# bb8.net
KiCad netlist of a schematic drawn in EAGLE
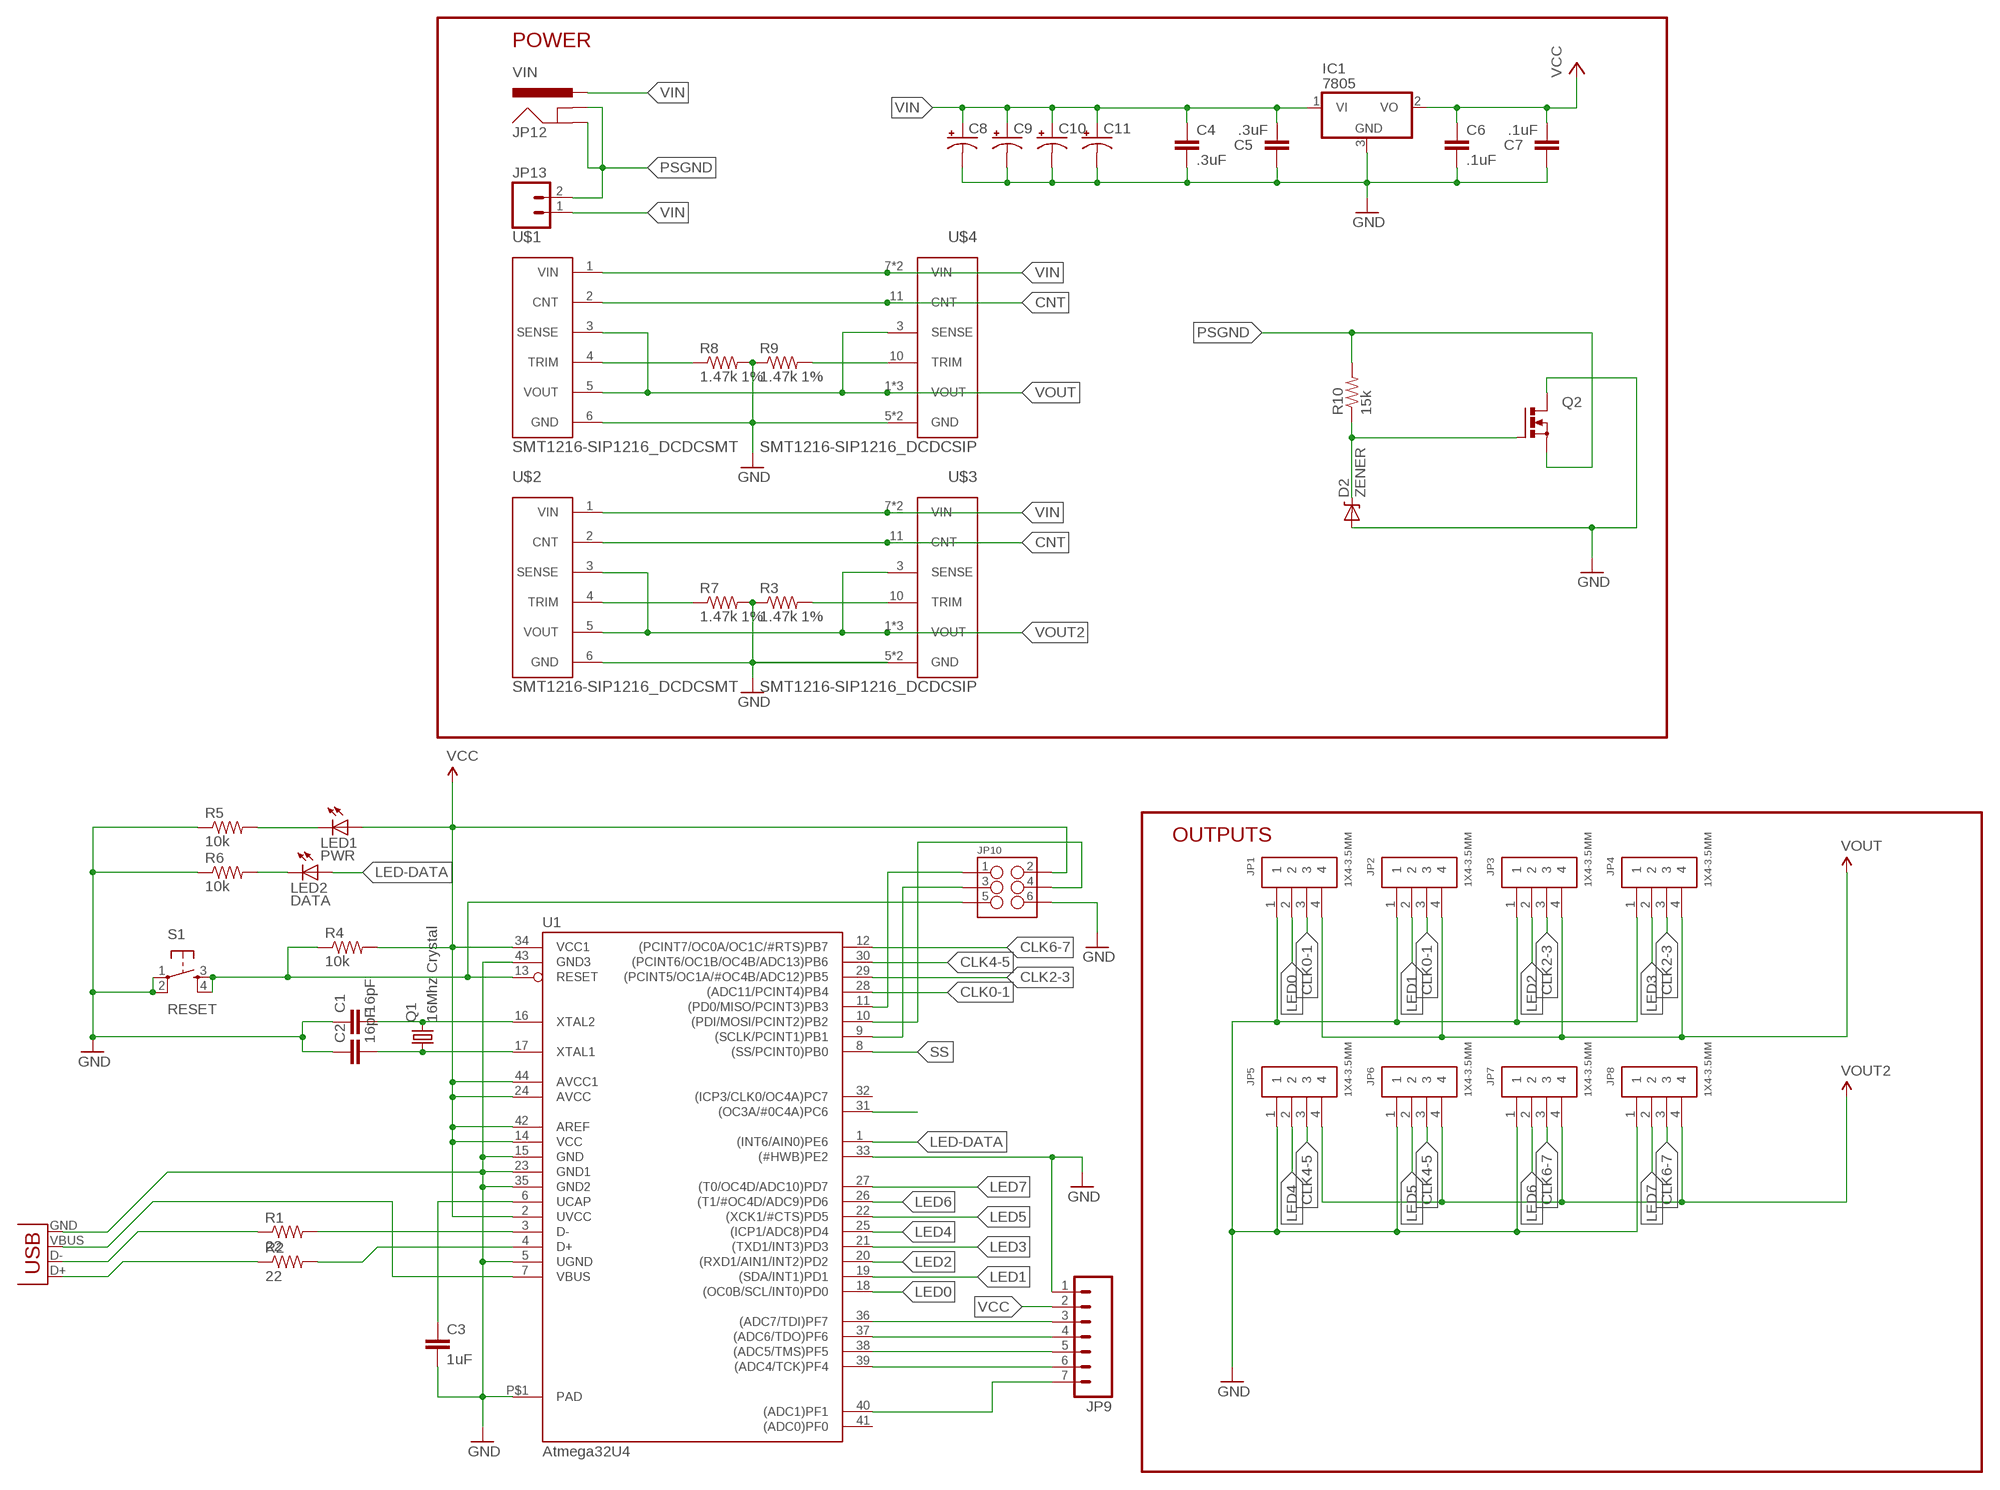
[diagram p0: schematic, sheet 1]

(export (version "E")
  (design (tool "Eeschema 10.0.6"))
  (components
    (comp (ref "C1")
      (value "16pF")
      (footprint "eagle-import:0805")
      (libsource (lib "eagle-import") (part "SparkFun-Passives_CAP0805"))
    )
    (comp (ref "C2")
      (value "16pF")
      (footprint "eagle-import:0805")
      (libsource (lib "eagle-import") (part "SparkFun-Passives_CAP0805"))
    )
    (comp (ref "C3")
      (value "1uF")
      (footprint "eagle-import:0805")
      (libsource (lib "eagle-import") (part "1UF-25V-10%(0805)"))
    )
    (comp (ref "C4")
      (value ".3uF")
      (footprint "eagle-import:1210")
      (libsource (lib "eagle-import") (part "CAP1210"))
    )
    (comp (ref "C5")
      (value ".3uF")
      (footprint "eagle-import:0805")
      (libsource (lib "eagle-import") (part "CAP0805"))
    )
    (comp (ref "C6")
      (value ".1uF")
      (footprint "eagle-import:1210")
      (libsource (lib "eagle-import") (part "CAP1210"))
    )
    (comp (ref "C7")
      (value ".1uF")
      (footprint "eagle-import:0805")
      (libsource (lib "eagle-import") (part "CAP0805"))
    )
    (comp (ref "C8")
      (value "CAP_POLE")
      (footprint "eagle-import:PANASONIC_E")
      (libsource (lib "eagle-import") (part "CAP_POLE"))
    )
    (comp (ref "C9")
      (value "CAP_POLE")
      (footprint "eagle-import:PANASONIC_E")
      (libsource (lib "eagle-import") (part "CAP_POLE"))
    )
    (comp (ref "C10")
      (value "CAP_POLE")
      (footprint "eagle-import:PANASONIC_E")
      (libsource (lib "eagle-import") (part "CAP_POLE"))
    )
    (comp (ref "C11")
      (value "CAP_POLE")
      (footprint "eagle-import:PANASONIC_E")
      (libsource (lib "eagle-import") (part "CAP_POLE"))
    )
    (comp (ref "D2")
      (value "ZENER")
      (footprint "eagle-import:SOD-323")
      (libsource (lib "eagle-import") (part "DIODE-ZENER-BZT52"))
    )
    (comp (ref "IC1")
      (value "7805")
      (footprint "eagle-import:TO252")
      (libsource (lib "eagle-import") (part "78DT06"))
    )
    (comp (ref "JP1")
      (value "1X4-3.5MM")
      (footprint "eagle-import:1X04-3.5MM")
      (libsource (lib "eagle-import") (part "1X4-3.5MM"))
    )
    (comp (ref "JP2")
      (value "1X4-3.5MM")
      (footprint "eagle-import:1X04-3.5MM")
      (libsource (lib "eagle-import") (part "1X4-3.5MM"))
    )
    (comp (ref "JP3")
      (value "1X4-3.5MM")
      (footprint "eagle-import:1X04-3.5MM")
      (libsource (lib "eagle-import") (part "1X4-3.5MM"))
    )
    (comp (ref "JP4")
      (value "1X4-3.5MM")
      (footprint "eagle-import:1X04-3.5MM")
      (libsource (lib "eagle-import") (part "1X4-3.5MM"))
    )
    (comp (ref "JP5")
      (value "1X4-3.5MM")
      (footprint "eagle-import:1X04-3.5MM")
      (libsource (lib "eagle-import") (part "1X4-3.5MM"))
    )
    (comp (ref "JP6")
      (value "1X4-3.5MM")
      (footprint "eagle-import:1X04-3.5MM")
      (libsource (lib "eagle-import") (part "1X4-3.5MM"))
    )
    (comp (ref "JP7")
      (value "1X4-3.5MM")
      (footprint "eagle-import:1X04-3.5MM")
      (libsource (lib "eagle-import") (part "1X4-3.5MM"))
    )
    (comp (ref "JP8")
      (value "1X4-3.5MM")
      (footprint "eagle-import:1X04-3.5MM")
      (libsource (lib "eagle-import") (part "1X4-3.5MM"))
    )
    (comp (ref "JP9")
      (value "M07")
      (footprint "eagle-import:1X07")
      (libsource (lib "eagle-import") (part "M07"))
    )
    (comp (ref "JP10")
      (value "M03X2POGO_PINS")
      (footprint "eagle-import:2X3_POGO")
      (libsource (lib "eagle-import") (part "M03X2POGO_PINS"))
    )
    (comp (ref "JP11")
      (value "USB-B")
      (footprint "eagle-import:USB-B-PTH")
      (libsource (lib "eagle-import") (part "USBPTH"))
    )
    (comp (ref "JP12")
      (value "VIN")
      (footprint "eagle-import:POWER_JACK_PTH_LOCK")
      (libsource (lib "eagle-import") (part "POWER_JACKPTH_LOCK"))
    )
    (comp (ref "JP13")
      (value "M025MM")
      (footprint "eagle-import:SCREWTERMINAL-5MM-2")
      (libsource (lib "eagle-import") (part "M025MM"))
    )
    (comp (ref "LED1")
      (value "PWR")
      (footprint "eagle-import:LED3MM")
      (libsource (lib "eagle-import") (part "LED3MM"))
    )
    (comp (ref "LED2")
      (value "DATA")
      (footprint "eagle-import:LED3MM")
      (libsource (lib "eagle-import") (part "LED3MM"))
    )
    (comp (ref "Q1")
      (value "16Mhz Crystal")
      (footprint "eagle-import:XS3225")
      (libsource (lib "eagle-import") (part "CRYSTAL"))
    )
    (comp (ref "Q2")
      (value "PMOSFET_NTO220BV")
      (footprint "eagle-import:TO220BV")
      (libsource (lib "eagle-import") (part "PMOSFET_NTO220BV"))
    )
    (comp (ref "R1")
      (value "22")
      (footprint "eagle-import:0805")
      (libsource (lib "eagle-import") (part "RESISTOR0805-RES"))
    )
    (comp (ref "R2")
      (value "22")
      (footprint "eagle-import:0805")
      (libsource (lib "eagle-import") (part "RESISTOR0805-RES"))
    )
    (comp (ref "R3")
      (value "1.47k 1%")
      (footprint "eagle-import:0805")
      (libsource (lib "eagle-import") (part "RESISTOR0805-RES"))
    )
    (comp (ref "R4")
      (value "10k")
      (footprint "eagle-import:0805")
      (libsource (lib "eagle-import") (part "RESISTOR0805-RES"))
    )
    (comp (ref "R5")
      (value "10k")
      (footprint "eagle-import:0805")
      (libsource (lib "eagle-import") (part "RESISTOR0805-RES"))
    )
    (comp (ref "R6")
      (value "10k")
      (footprint "eagle-import:0805")
      (libsource (lib "eagle-import") (part "RESISTOR0805-RES"))
    )
    (comp (ref "R7")
      (value "1.47k 1%")
      (footprint "eagle-import:0805")
      (libsource (lib "eagle-import") (part "RESISTOR0805-RES"))
    )
    (comp (ref "R8")
      (value "1.47k 1%")
      (footprint "eagle-import:0805")
      (libsource (lib "eagle-import") (part "RESISTOR0805-RES"))
    )
    (comp (ref "R9")
      (value "1.47k 1%")
      (footprint "eagle-import:0805")
      (libsource (lib "eagle-import") (part "RESISTOR0805-RES"))
    )
    (comp (ref "R10")
      (value "15k")
      (footprint "eagle-import:0805")
      (libsource (lib "eagle-import") (part "RESISTOR0805-RES"))
    )
    (comp (ref "S1")
      (value "RESET")
      (footprint "eagle-import:TACTILE_SWITCH_SMD")
      (libsource (lib "eagle-import") (part "TAC_SWITCHSMD"))
    )
    (comp (ref "U$1")
      (value "SMT1216-SIP1216_DCDCSMT")
      (footprint "eagle-import:SMT1216_DCDC")
      (libsource (lib "eagle-import") (part "SMT1216-SIP1216_DCDCSMT"))
    )
    (comp (ref "U$2")
      (value "SMT1216-SIP1216_DCDCSMT")
      (footprint "eagle-import:SMT1216_DCDC")
      (libsource (lib "eagle-import") (part "SMT1216-SIP1216_DCDCSMT"))
    )
    (comp (ref "U$3")
      (value "SMT1216-SIP1216_DCDCSIP")
      (footprint "eagle-import:SIP1216_DCDC")
      (libsource (lib "eagle-import") (part "SMT1216-SIP1216_DCDCSIP"))
    )
    (comp (ref "U$4")
      (value "SMT1216-SIP1216_DCDCSIP")
      (footprint "eagle-import:SIP1216_DCDC")
      (libsource (lib "eagle-import") (part "SMT1216-SIP1216_DCDCSIP"))
    )
    (comp (ref "U1")
      (value "Atmega32U4")
      (footprint "eagle-import:ARDUINO_LEONARDO-REV3B_SMARTPRJ_TQFP44-PAD")
      (libsource (lib "eagle-import") (part "ARDUINO_LEONARDO-REV3B_SMARTPRJ_ATMEGA32U4-XUAU"))
    )
  )
  (nets
    (net (code "1") (name "CLK0-1") (class "Default")
      (node (ref "JP1") (pin "3") (pinfunction "3_3") (pintype "bidirectional"))
      (node (ref "JP2") (pin "3") (pinfunction "3_3") (pintype "bidirectional"))
      (node (ref "U1") (pin "28") (pinfunction "(ADC11/PCINT4)PB4_28") (pintype "bidirectional"))
    )
    (net (code "2") (name "CLK2-3") (class "Default")
      (node (ref "JP3") (pin "3") (pinfunction "3_3") (pintype "bidirectional"))
      (node (ref "JP4") (pin "3") (pinfunction "3_3") (pintype "bidirectional"))
      (node (ref "U1") (pin "29") (pinfunction "(PCINT5/OC1A/#OC4B/ADC12)PB5_29") (pintype "bidirectional"))
    )
    (net (code "3") (name "CLK4-5") (class "Default")
      (node (ref "JP5") (pin "3") (pinfunction "3_3") (pintype "bidirectional"))
      (node (ref "JP6") (pin "3") (pinfunction "3_3") (pintype "bidirectional"))
      (node (ref "U1") (pin "30") (pinfunction "(PCINT6/OC1B/OC4B/ADC13)PB6_30") (pintype "bidirectional"))
    )
    (net (code "4") (name "CLK6-7") (class "Default")
      (node (ref "JP7") (pin "3") (pinfunction "3_3") (pintype "bidirectional"))
      (node (ref "JP8") (pin "3") (pinfunction "3_3") (pintype "bidirectional"))
      (node (ref "U1") (pin "12") (pinfunction "(PCINT7/OC0A/OC1C/#RTS)PB7_12") (pintype "bidirectional"))
    )
    (net (code "5") (name "CNT") (class "Default")
      (node (ref "U$1") (pin "2") (pinfunction "CNT_2") (pintype "bidirectional"))
      (node (ref "U$2") (pin "2") (pinfunction "CNT_2") (pintype "bidirectional"))
      (node (ref "U$3") (pin "11") (pinfunction "CNT_11") (pintype "bidirectional"))
      (node (ref "U$4") (pin "11") (pinfunction "CNT_11") (pintype "bidirectional"))
      (node (ref "U1") (pin "31") (pinfunction "(OC3A/#0C4A)PC6_31") (pintype "bidirectional"))
    )
    (net (code "6") (name "GND") (class "Default")
      (node (ref "C1") (pin "1") (pinfunction "1_1") (pintype "passive"))
      (node (ref "C10") (pin "-") (pinfunction "-_-") (pintype "passive"))
      (node (ref "C11") (pin "-") (pinfunction "-_-") (pintype "passive"))
      (node (ref "C2") (pin "1") (pinfunction "1_1") (pintype "passive"))
      (node (ref "C3") (pin "2") (pinfunction "2_2") (pintype "passive"))
      (node (ref "C4") (pin "2") (pinfunction "2_2") (pintype "passive"))
      (node (ref "C5") (pin "1") (pinfunction "1_1") (pintype "passive"))
      (node (ref "C6") (pin "2") (pinfunction "2_2") (pintype "passive"))
      (node (ref "C7") (pin "1") (pinfunction "1_1") (pintype "passive"))
      (node (ref "C8") (pin "-") (pinfunction "-_-") (pintype "passive"))
      (node (ref "C9") (pin "-") (pinfunction "-_-") (pintype "passive"))
      (node (ref "D2") (pin "2") (pinfunction "A_2") (pintype "passive"))
      (node (ref "IC1") (pin "3") (pinfunction "GND_3") (pintype "passive"))
      (node (ref "JP1") (pin "1") (pinfunction "1_1") (pintype "bidirectional"))
      (node (ref "JP10") (pin "P$6") (pinfunction "6_P$6") (pintype "bidirectional"))
      (node (ref "JP11") (pin "GND") (pinfunction "GND_GND") (pintype "bidirectional"))
      (node (ref "JP2") (pin "1") (pinfunction "1_1") (pintype "bidirectional"))
      (node (ref "JP3") (pin "1") (pinfunction "1_1") (pintype "bidirectional"))
      (node (ref "JP4") (pin "1") (pinfunction "1_1") (pintype "bidirectional"))
      (node (ref "JP5") (pin "1") (pinfunction "1_1") (pintype "bidirectional"))
      (node (ref "JP6") (pin "1") (pinfunction "1_1") (pintype "bidirectional"))
      (node (ref "JP7") (pin "1") (pinfunction "1_1") (pintype "bidirectional"))
      (node (ref "JP8") (pin "1") (pinfunction "1_1") (pintype "bidirectional"))
      (node (ref "JP9") (pin "1") (pinfunction "1_1") (pintype "passive"))
      (node (ref "Q2") (pin "D") (pinfunction "D_D") (pintype "passive"))
      (node (ref "R3") (pin "1") (pinfunction "1_1") (pintype "passive"))
      (node (ref "R5") (pin "1") (pinfunction "1_1") (pintype "passive"))
      (node (ref "R6") (pin "1") (pinfunction "1_1") (pintype "passive"))
      (node (ref "R7") (pin "2") (pinfunction "2_2") (pintype "passive"))
      (node (ref "R8") (pin "2") (pinfunction "2_2") (pintype "passive"))
      (node (ref "R9") (pin "1") (pinfunction "1_1") (pintype "passive"))
      (node (ref "S1") (pin "1") (pinfunction "1_1") (pintype "passive"))
      (node (ref "S1") (pin "2") (pinfunction "2_2") (pintype "passive"))
      (node (ref "U$1") (pin "6") (pinfunction "GND_6") (pintype "bidirectional"))
      (node (ref "U$2") (pin "6") (pinfunction "GND_6") (pintype "bidirectional"))
      (node (ref "U$3") (pin "5") (pinfunction "GND_5") (pintype "bidirectional"))
      (node (ref "U$3") (pin "6") (pinfunction "GND_6") (pintype "bidirectional"))
      (node (ref "U$4") (pin "5") (pinfunction "GND_5") (pintype "bidirectional"))
      (node (ref "U$4") (pin "6") (pinfunction "GND_6") (pintype "bidirectional"))
      (node (ref "U1") (pin "15") (pinfunction "GND_15") (pintype "power_in"))
      (node (ref "U1") (pin "23") (pinfunction "GND1_23") (pintype "power_in"))
      (node (ref "U1") (pin "33") (pinfunction "(#HWB)PE2_33") (pintype "bidirectional"))
      (node (ref "U1") (pin "35") (pinfunction "GND2_35") (pintype "power_in"))
      (node (ref "U1") (pin "43") (pinfunction "GND3_43") (pintype "power_in"))
      (node (ref "U1") (pin "5") (pinfunction "UGND_5") (pintype "power_in"))
      (node (ref "U1") (pin "P$1") (pinfunction "PAD_P$1") (pintype "power_in"))
    )
    (net (code "7") (name "LED-DATA") (class "Default")
      (node (ref "LED2") (pin "A") (pinfunction "A_A") (pintype "passive"))
      (node (ref "U1") (pin "1") (pinfunction "(INT6/AIN0)PE6_1") (pintype "bidirectional"))
    )
    (net (code "8") (name "LED0") (class "Default")
      (node (ref "JP1") (pin "2") (pinfunction "2_2") (pintype "bidirectional"))
      (node (ref "U1") (pin "18") (pinfunction "(OC0B/SCL/INT0)PD0_18") (pintype "bidirectional"))
    )
    (net (code "9") (name "LED1") (class "Default")
      (node (ref "JP2") (pin "2") (pinfunction "2_2") (pintype "bidirectional"))
      (node (ref "U1") (pin "19") (pinfunction "(SDA/INT1)PD1_19") (pintype "bidirectional"))
    )
    (net (code "10") (name "LED2") (class "Default")
      (node (ref "JP3") (pin "2") (pinfunction "2_2") (pintype "bidirectional"))
      (node (ref "U1") (pin "20") (pinfunction "(RXD1/AIN1/INT2)PD2_20") (pintype "bidirectional"))
    )
    (net (code "11") (name "LED3") (class "Default")
      (node (ref "JP4") (pin "2") (pinfunction "2_2") (pintype "bidirectional"))
      (node (ref "U1") (pin "21") (pinfunction "(TXD1/INT3)PD3_21") (pintype "bidirectional"))
    )
    (net (code "12") (name "LED4") (class "Default")
      (node (ref "JP5") (pin "2") (pinfunction "2_2") (pintype "bidirectional"))
      (node (ref "U1") (pin "25") (pinfunction "(ICP1/ADC8)PD4_25") (pintype "bidirectional"))
    )
    (net (code "13") (name "LED5") (class "Default")
      (node (ref "JP6") (pin "2") (pinfunction "2_2") (pintype "bidirectional"))
      (node (ref "U1") (pin "22") (pinfunction "(XCK1/#CTS)PD5_22") (pintype "bidirectional"))
    )
    (net (code "14") (name "LED6") (class "Default")
      (node (ref "JP7") (pin "2") (pinfunction "2_2") (pintype "bidirectional"))
      (node (ref "U1") (pin "26") (pinfunction "(T1/#OC4D/ADC9)PD6_26") (pintype "bidirectional"))
    )
    (net (code "15") (name "LED7") (class "Default")
      (node (ref "JP8") (pin "2") (pinfunction "2_2") (pintype "bidirectional"))
      (node (ref "U1") (pin "27") (pinfunction "(T0/OC4D/ADC10)PD7_27") (pintype "bidirectional"))
    )
    (net (code "16") (name "Net-(D2-C)") (class "Default")
      (node (ref "D2") (pin "1") (pinfunction "C_1") (pintype "passive"))
      (node (ref "Q2") (pin "G") (pinfunction "G_G") (pintype "passive"))
      (node (ref "R10") (pin "1") (pinfunction "1_1") (pintype "passive"))
    )
    (net (code "17") (name "Net-(JP10-1)") (class "Default")
      (node (ref "JP10") (pin "P$1") (pinfunction "1_P$1") (pintype "bidirectional"))
      (node (ref "U1") (pin "11") (pinfunction "(PD0/MISO/PCINT3)PB3_11") (pintype "bidirectional"))
    )
    (net (code "18") (name "Net-(JP10-3)") (class "Default")
      (node (ref "JP10") (pin "P$3") (pinfunction "3_P$3") (pintype "bidirectional"))
      (node (ref "U1") (pin "9") (pinfunction "(SCLK/PCINT1)PB1_9") (pintype "bidirectional"))
    )
    (net (code "19") (name "Net-(JP10-4)") (class "Default")
      (node (ref "JP10") (pin "P$4") (pinfunction "4_P$4") (pintype "bidirectional"))
      (node (ref "U1") (pin "10") (pinfunction "(PDI/MOSI/PCINT2)PB2_10") (pintype "bidirectional"))
    )
    (net (code "20") (name "Net-(JP10-5)") (class "Default")
      (node (ref "JP10") (pin "P$5") (pinfunction "5_P$5") (pintype "bidirectional"))
      (node (ref "R4") (pin "1") (pinfunction "1_1") (pintype "passive"))
      (node (ref "S1") (pin "3") (pinfunction "3_3") (pintype "passive"))
      (node (ref "S1") (pin "4") (pinfunction "4_4") (pintype "passive"))
      (node (ref "U1") (pin "13") (pinfunction "RESET_13") (pintype "input"))
    )
    (net (code "21") (name "Net-(JP11-PadD+)") (class "Default")
      (node (ref "JP11") (pin "D+") (pinfunction "D+_D+") (pintype "bidirectional"))
      (node (ref "R2") (pin "1") (pinfunction "1_1") (pintype "passive"))
    )
    (net (code "22") (name "Net-(JP11-PadD-)") (class "Default")
      (node (ref "JP11") (pin "D-") (pinfunction "D-_D-") (pintype "bidirectional"))
      (node (ref "R1") (pin "1") (pinfunction "1_1") (pintype "passive"))
    )
    (net (code "23") (name "Net-(LED1-C)") (class "Default")
      (node (ref "LED1") (pin "K") (pinfunction "C_K") (pintype "passive"))
      (node (ref "R5") (pin "2") (pinfunction "2_2") (pintype "passive"))
    )
    (net (code "24") (name "Net-(LED2-C)") (class "Default")
      (node (ref "LED2") (pin "K") (pinfunction "C_K") (pintype "passive"))
      (node (ref "R6") (pin "2") (pinfunction "2_2") (pintype "passive"))
    )
    (net (code "25") (name "Net-(Q1-1)") (class "Default")
      (node (ref "C2") (pin "2") (pinfunction "2_2") (pintype "passive"))
      (node (ref "Q1") (pin "P$1") (pinfunction "1_P$1") (pintype "passive"))
      (node (ref "U1") (pin "17") (pinfunction "XTAL1_17") (pintype "bidirectional"))
    )
    (net (code "26") (name "Net-(Q1-2)") (class "Default")
      (node (ref "C1") (pin "2") (pinfunction "2_2") (pintype "passive"))
      (node (ref "Q1") (pin "P$3") (pinfunction "2_P$3") (pintype "passive"))
      (node (ref "U1") (pin "16") (pinfunction "XTAL2_16") (pintype "bidirectional"))
    )
    (net (code "27") (name "Net-(U$1-TRIM)") (class "Default")
      (node (ref "R8") (pin "1") (pinfunction "1_1") (pintype "passive"))
      (node (ref "U$1") (pin "4") (pinfunction "TRIM_4") (pintype "bidirectional"))
    )
    (net (code "28") (name "Net-(U$2-TRIM)") (class "Default")
      (node (ref "R7") (pin "1") (pinfunction "1_1") (pintype "passive"))
      (node (ref "U$2") (pin "4") (pinfunction "TRIM_4") (pintype "bidirectional"))
    )
    (net (code "29") (name "Net-(U$3-TRIM)") (class "Default")
      (node (ref "R3") (pin "2") (pinfunction "2_2") (pintype "passive"))
      (node (ref "U$3") (pin "10") (pinfunction "TRIM_10") (pintype "bidirectional"))
    )
    (net (code "30") (name "Net-(U$4-TRIM)") (class "Default")
      (node (ref "R9") (pin "2") (pinfunction "2_2") (pintype "passive"))
      (node (ref "U$4") (pin "10") (pinfunction "TRIM_10") (pintype "bidirectional"))
    )
    (net (code "31") (name "Net-(U1-(ADC1)PF1)") (class "Default")
      (node (ref "JP9") (pin "7") (pinfunction "7_7") (pintype "passive"))
      (node (ref "U1") (pin "40") (pinfunction "(ADC1)PF1_40") (pintype "bidirectional"))
    )
    (net (code "32") (name "Net-(U1-(ADC4{slash}TCK)PF4)") (class "Default")
      (node (ref "JP9") (pin "6") (pinfunction "6_6") (pintype "passive"))
      (node (ref "U1") (pin "39") (pinfunction "(ADC4/TCK)PF4_39") (pintype "bidirectional"))
    )
    (net (code "33") (name "Net-(U1-(ADC5{slash}TMS)PF5)") (class "Default")
      (node (ref "JP9") (pin "5") (pinfunction "5_5") (pintype "passive"))
      (node (ref "U1") (pin "38") (pinfunction "(ADC5/TMS)PF5_38") (pintype "bidirectional"))
    )
    (net (code "34") (name "Net-(U1-(ADC6{slash}TDO)PF6)") (class "Default")
      (node (ref "JP9") (pin "4") (pinfunction "4_4") (pintype "passive"))
      (node (ref "U1") (pin "37") (pinfunction "(ADC6/TDO)PF6_37") (pintype "bidirectional"))
    )
    (net (code "35") (name "Net-(U1-(ADC7{slash}TDI)PF7)") (class "Default")
      (node (ref "JP9") (pin "3") (pinfunction "3_3") (pintype "passive"))
      (node (ref "U1") (pin "36") (pinfunction "(ADC7/TDI)PF7_36") (pintype "bidirectional"))
    )
    (net (code "36") (name "Net-(U1-D+)") (class "Default")
      (node (ref "R2") (pin "2") (pinfunction "2_2") (pintype "passive"))
      (node (ref "U1") (pin "4") (pinfunction "D+_4") (pintype "bidirectional"))
    )
    (net (code "37") (name "Net-(U1-D-)") (class "Default")
      (node (ref "R1") (pin "2") (pinfunction "2_2") (pintype "passive"))
      (node (ref "U1") (pin "3") (pinfunction "D-_3") (pintype "bidirectional"))
    )
    (net (code "38") (name "Net-(U1-UCAP)") (class "Default")
      (node (ref "C3") (pin "1") (pinfunction "1_1") (pintype "passive"))
      (node (ref "U1") (pin "6") (pinfunction "UCAP_6") (pintype "passive"))
    )
    (net (code "39") (name "Net-(U1-VBUS)") (class "Default")
      (node (ref "JP11") (pin "VBUS") (pinfunction "VBUS_VBUS") (pintype "bidirectional"))
      (node (ref "U1") (pin "7") (pinfunction "VBUS_7") (pintype "input"))
    )
    (net (code "40") (name "PSGND") (class "Default")
      (node (ref "JP12") (pin "GND") (pinfunction "GND_GND") (pintype "bidirectional"))
      (node (ref "JP12") (pin "GNDBREAK") (pinfunction "GNDBREAK_GNDBREAK") (pintype "bidirectional"))
      (node (ref "JP13") (pin "2") (pinfunction "2_2") (pintype "passive"))
      (node (ref "Q2") (pin "S") (pinfunction "S_S") (pintype "passive"))
      (node (ref "R10") (pin "2") (pinfunction "2_2") (pintype "passive"))
    )
    (net (code "41") (name "SS") (class "Default")
      (node (ref "U1") (pin "8") (pinfunction "(SS/PCINT0)PB0_8") (pintype "bidirectional"))
    )
    (net (code "42") (name "VCC") (class "Default")
      (node (ref "C6") (pin "1") (pinfunction "1_1") (pintype "passive"))
      (node (ref "C7") (pin "2") (pinfunction "2_2") (pintype "passive"))
      (node (ref "IC1") (pin "2") (pinfunction "VO_2") (pintype "passive"))
      (node (ref "JP10") (pin "P$2") (pinfunction "2_P$2") (pintype "bidirectional"))
      (node (ref "JP9") (pin "2") (pinfunction "2_2") (pintype "passive"))
      (node (ref "LED1") (pin "A") (pinfunction "A_A") (pintype "passive"))
      (node (ref "R4") (pin "2") (pinfunction "2_2") (pintype "passive"))
      (node (ref "U1") (pin "14") (pinfunction "VCC_14") (pintype "power_in"))
      (node (ref "U1") (pin "2") (pinfunction "UVCC_2") (pintype "power_in"))
      (node (ref "U1") (pin "24") (pinfunction "AVCC_24") (pintype "power_in"))
      (node (ref "U1") (pin "34") (pinfunction "VCC1_34") (pintype "power_in"))
      (node (ref "U1") (pin "42") (pinfunction "AREF_42") (pintype "power_in"))
      (node (ref "U1") (pin "44") (pinfunction "AVCC1_44") (pintype "power_in"))
    )
    (net (code "43") (name "VIN") (class "Default")
      (node (ref "C10") (pin "+") (pinfunction "+_+") (pintype "passive"))
      (node (ref "C11") (pin "+") (pinfunction "+_+") (pintype "passive"))
      (node (ref "C4") (pin "1") (pinfunction "1_1") (pintype "passive"))
      (node (ref "C5") (pin "2") (pinfunction "2_2") (pintype "passive"))
      (node (ref "C8") (pin "+") (pinfunction "+_+") (pintype "passive"))
      (node (ref "C9") (pin "+") (pinfunction "+_+") (pintype "passive"))
      (node (ref "IC1") (pin "1") (pinfunction "VI_1") (pintype "input"))
      (node (ref "JP12") (pin "PWR") (pinfunction "PWR_PWR") (pintype "bidirectional"))
      (node (ref "JP13") (pin "1") (pinfunction "1_1") (pintype "passive"))
      (node (ref "U$1") (pin "1") (pinfunction "VIN_1") (pintype "bidirectional"))
      (node (ref "U$2") (pin "1") (pinfunction "VIN_1") (pintype "bidirectional"))
      (node (ref "U$3") (pin "7") (pinfunction "VIN_7") (pintype "bidirectional"))
      (node (ref "U$3") (pin "8") (pinfunction "VIN_8") (pintype "bidirectional"))
      (node (ref "U$4") (pin "7") (pinfunction "VIN_7") (pintype "bidirectional"))
      (node (ref "U$4") (pin "8") (pinfunction "VIN_8") (pintype "bidirectional"))
    )
    (net (code "44") (name "VOUT") (class "Default")
      (node (ref "JP1") (pin "4") (pinfunction "4_4") (pintype "bidirectional"))
      (node (ref "JP2") (pin "4") (pinfunction "4_4") (pintype "bidirectional"))
      (node (ref "JP3") (pin "4") (pinfunction "4_4") (pintype "bidirectional"))
      (node (ref "JP4") (pin "4") (pinfunction "4_4") (pintype "bidirectional"))
      (node (ref "U$1") (pin "3") (pinfunction "SENSE_3") (pintype "bidirectional"))
      (node (ref "U$1") (pin "5") (pinfunction "VOUT_5") (pintype "bidirectional"))
      (node (ref "U$4") (pin "1") (pinfunction "VOUT_1") (pintype "bidirectional"))
      (node (ref "U$4") (pin "2") (pinfunction "VOUT_2") (pintype "bidirectional"))
      (node (ref "U$4") (pin "3") (pinfunction "SENSE_3") (pintype "bidirectional"))
      (node (ref "U$4") (pin "4") (pinfunction "VOUT_4") (pintype "bidirectional"))
    )
    (net (code "45") (name "VOUT2") (class "Default")
      (node (ref "JP5") (pin "4") (pinfunction "4_4") (pintype "bidirectional"))
      (node (ref "JP6") (pin "4") (pinfunction "4_4") (pintype "bidirectional"))
      (node (ref "JP7") (pin "4") (pinfunction "4_4") (pintype "bidirectional"))
      (node (ref "JP8") (pin "4") (pinfunction "4_4") (pintype "bidirectional"))
      (node (ref "U$2") (pin "3") (pinfunction "SENSE_3") (pintype "bidirectional"))
      (node (ref "U$2") (pin "5") (pinfunction "VOUT_5") (pintype "bidirectional"))
      (node (ref "U$3") (pin "1") (pinfunction "VOUT_1") (pintype "bidirectional"))
      (node (ref "U$3") (pin "2") (pinfunction "VOUT_2") (pintype "bidirectional"))
      (node (ref "U$3") (pin "3") (pinfunction "SENSE_3") (pintype "bidirectional"))
      (node (ref "U$3") (pin "4") (pinfunction "VOUT_4") (pintype "bidirectional"))
    )
    (net (code "46") (name "unconnected-(U1-(ADC0)PF0-Pad41)") (class "Default")
      (node (ref "U1") (pin "41") (pinfunction "(ADC0)PF0_41") (pintype "bidirectional"))
    )
    (net (code "47") (name "unconnected-(U1-(ICP3{slash}CLK0{slash}OC4A)PC7-Pad32)") (class "Default")
      (node (ref "U1") (pin "32") (pinfunction "(ICP3/CLK0/OC4A)PC7_32") (pintype "bidirectional"))
    )
  )
)
